# Easy_555_relay.net
KiCad netlist of a schematic drawn in EAGLE
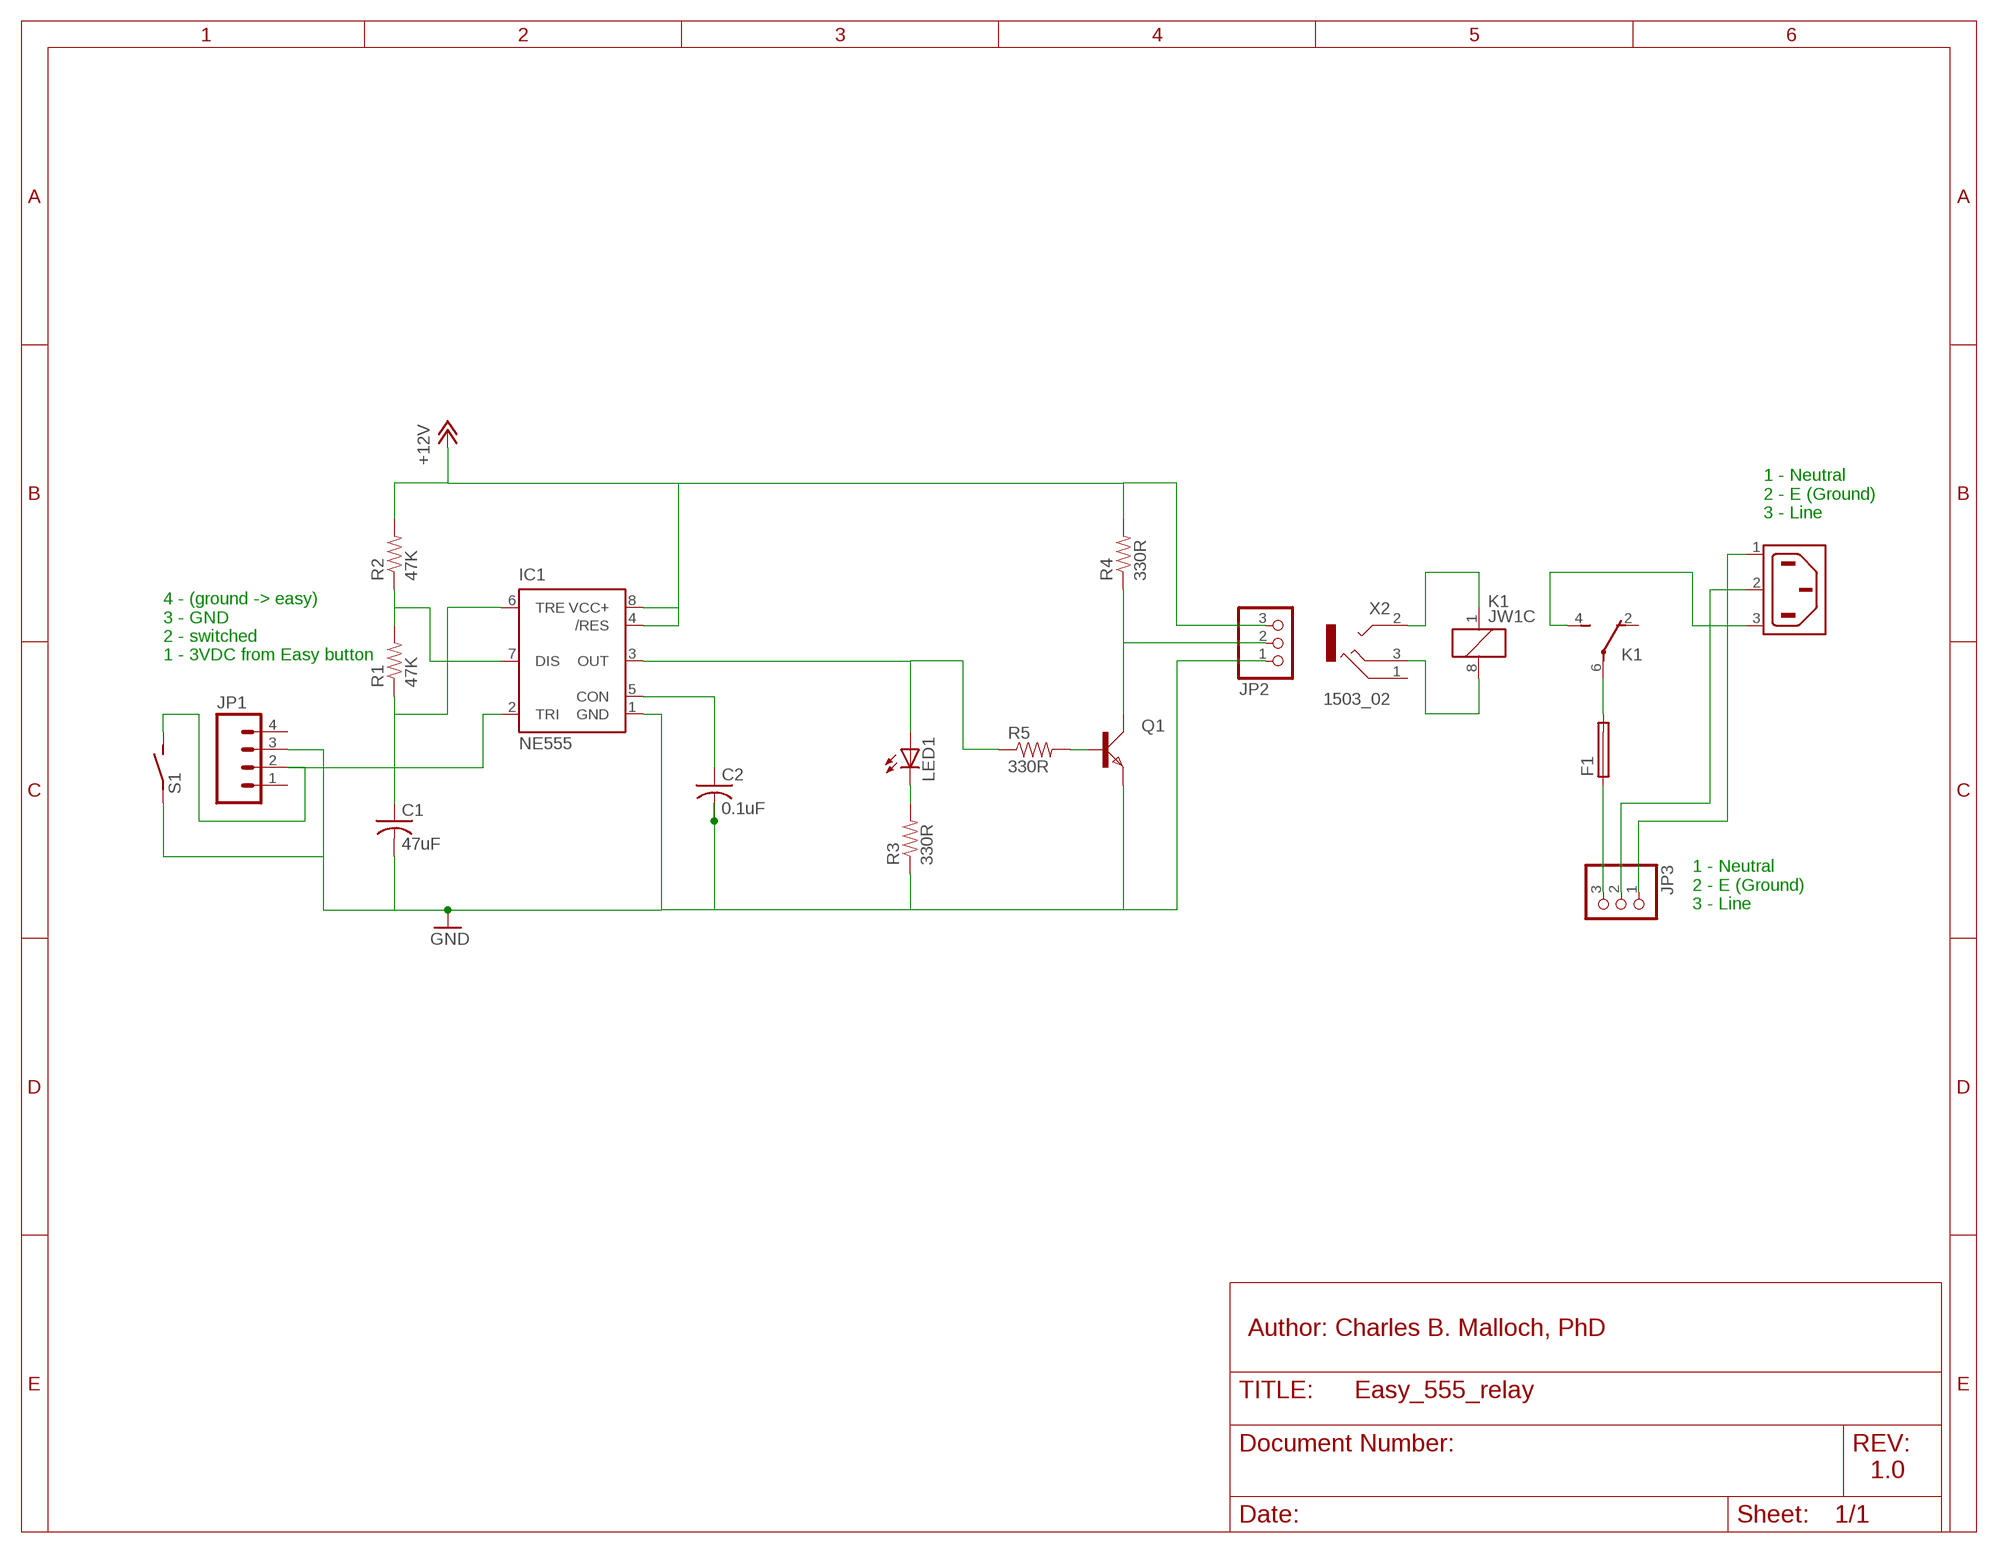
[diagram p0: schematic, sheet 1]

(export (version "E")
  (design (tool "Eeschema 10.0.6"))
  (components
    (comp (ref "C1")
      (value "47uF")
      (footprint "eagle-import:C050-030X075")
      (libsource (lib "eagle-import") (part "resistor_C-US050-030X075"))
    )
    (comp (ref "C2")
      (value "0.1uF")
      (footprint "eagle-import:C025-025X050")
      (libsource (lib "eagle-import") (part "C-US025-025X050"))
    )
    (comp (ref "F1")
      (value "GSH15")
      (footprint "eagle-import:GSH15")
      (fields (field (name "MPN") "64900001039"))
      (libsource (lib "eagle-import") (part "GSH15"))
    )
    (comp (ref "IC1")
      (value "NE555")
      (footprint "eagle-import:DIL-08")
      (fields (field (name "MF") "Arrow Electronics") (field (name "MPN") "NE555N"))
      (libsource (lib "eagle-import") (part "NE555"))
    )
    (comp (ref "JP1")
      (value "M04LOCK")
      (footprint "eagle-import:1X04_LOCK")
      (libsource (lib "eagle-import") (part "M04LOCK"))
    )
    (comp (ref "JP2")
      (value "PINHD-1X3")
      (footprint "eagle-import:1X03")
      (libsource (lib "eagle-import") (part "PINHD-1X3"))
    )
    (comp (ref "JP3")
      (value "PINHD-1X3")
      (footprint "eagle-import:1X03")
      (libsource (lib "eagle-import") (part "PINHD-1X3"))
    )
    (comp (ref "K1")
      (value "JW1C")
      (footprint "eagle-import:JW1C")
      (libsource (lib "eagle-import") (part "JW1C"))
    )
    (comp (ref "LED1")
      (value "LED3MM")
      (footprint "eagle-import:LED3MM")
      (libsource (lib "eagle-import") (part "LED3MM"))
    )
    (comp (ref "Q1")
      (value "2N3904-")
      (footprint "eagle-import:TO92D-")
      (libsource (lib "eagle-import") (part "2N3904-"))
    )
    (comp (ref "R1")
      (value "47K")
      (footprint "eagle-import:AXIAL-0.4")
      (libsource (lib "eagle-import") (part "RESISTORPTH-1/4W"))
    )
    (comp (ref "R2")
      (value "47K")
      (footprint "eagle-import:AXIAL-0.4")
      (libsource (lib "eagle-import") (part "RESISTORPTH-1/4W"))
    )
    (comp (ref "R3")
      (value "330R")
      (footprint "eagle-import:AXIAL-0.4")
      (libsource (lib "eagle-import") (part "RESISTORPTH-1/4W"))
    )
    (comp (ref "R4")
      (value "330R")
      (footprint "eagle-import:AXIAL-0.4")
      (libsource (lib "eagle-import") (part "RESISTORPTH-1/4W"))
    )
    (comp (ref "R5")
      (value "330R")
      (footprint "eagle-import:AXIAL-0.4")
      (libsource (lib "eagle-import") (part "RESISTORPTH-1/4W"))
    )
    (comp (ref "S1")
      (value "SPST2EVQPJ")
      (footprint "eagle-import:EVQPJ")
      (libsource (lib "eagle-import") (part "SPST2EVQPJ"))
    )
    (comp (ref "X1")
      (value "6ESRM-P")
      (footprint "eagle-import:6ESRM-P")
      (fields (field (name "MF") "TYCO ELECTRONICS"))
      (libsource (lib "eagle-import") (part "6ESRM-P"))
    )
    (comp (ref "X2")
      (value "1503_02")
      (footprint "eagle-import:1503_02")
      (libsource (lib "eagle-import") (part "1503_02"))
    )
  )
  (nets
    (net (code "1") (name "+12V") (class "Default")
      (node (ref "IC1") (pin "4") (pinfunction "/RES_4") (pintype "input"))
      (node (ref "IC1") (pin "8") (pinfunction "VCC+_8") (pintype "power_in"))
      (node (ref "JP2") (pin "3") (pinfunction "3_3") (pintype "passive"))
      (node (ref "R2") (pin "P$2") (pinfunction "2_P$2") (pintype "passive"))
      (node (ref "R4") (pin "P$2") (pinfunction "2_P$2") (pintype "passive"))
    )
    (net (code "2") (name "GND") (class "Default")
      (node (ref "C1") (pin "2") (pinfunction "2_2") (pintype "passive"))
      (node (ref "C2") (pin "2") (pinfunction "2_2") (pintype "passive"))
      (node (ref "IC1") (pin "1") (pinfunction "GND_1") (pintype "power_in"))
      (node (ref "JP1") (pin "3") (pinfunction "3_3") (pintype "passive"))
      (node (ref "JP2") (pin "1") (pinfunction "1_1") (pintype "passive"))
      (node (ref "Q1") (pin "E") (pinfunction "E_E") (pintype "passive"))
      (node (ref "R3") (pin "P$1") (pinfunction "1_P$1") (pintype "passive"))
      (node (ref "S1") (pin "A") (pinfunction "1_A") (pintype "passive"))
    )
    (net (code "3") (name "Net-(F1-Pad1)") (class "Default")
      (node (ref "F1") (pin "1") (pinfunction "1_1") (pintype "passive"))
      (node (ref "JP3") (pin "3") (pinfunction "3_3") (pintype "passive"))
    )
    (net (code "4") (name "Net-(IC1-CON)") (class "Default")
      (node (ref "C2") (pin "1") (pinfunction "1_1") (pintype "passive"))
      (node (ref "IC1") (pin "5") (pinfunction "CON_5") (pintype "input"))
    )
    (net (code "5") (name "Net-(IC1-DIS)") (class "Default")
      (node (ref "IC1") (pin "7") (pinfunction "DIS_7") (pintype "input"))
      (node (ref "R1") (pin "P$2") (pinfunction "2_P$2") (pintype "passive"))
      (node (ref "R2") (pin "P$1") (pinfunction "1_P$1") (pintype "passive"))
    )
    (net (code "6") (name "Net-(IC1-OUT)") (class "Default")
      (node (ref "IC1") (pin "3") (pinfunction "OUT_3") (pintype "output"))
      (node (ref "LED1") (pin "A") (pinfunction "A_A") (pintype "passive"))
      (node (ref "R5") (pin "P$1") (pinfunction "1_P$1") (pintype "passive"))
    )
    (net (code "7") (name "Net-(IC1-TRE)") (class "Default")
      (node (ref "C1") (pin "1") (pinfunction "1_1") (pintype "passive"))
      (node (ref "IC1") (pin "6") (pinfunction "TRE_6") (pintype "input"))
      (node (ref "R1") (pin "P$1") (pinfunction "1_P$1") (pintype "passive"))
    )
    (net (code "8") (name "Net-(IC1-TRI)") (class "Default")
      (node (ref "IC1") (pin "2") (pinfunction "TRI_2") (pintype "input"))
      (node (ref "JP1") (pin "2") (pinfunction "2_2") (pintype "passive"))
      (node (ref "S1") (pin "B") (pinfunction "2_B") (pintype "passive"))
    )
    (net (code "9") (name "Net-(K1-Pad1)") (class "Default")
      (node (ref "K1") (pin "1") (pinfunction "1_1") (pintype "passive"))
      (node (ref "X2") (pin "2") (pinfunction "2_2") (pintype "passive"))
    )
    (net (code "10") (name "Net-(K1A-P)") (class "Default")
      (node (ref "F1") (pin "2") (pinfunction "2_2") (pintype "passive"))
      (node (ref "K1") (pin "6") (pinfunction "P_6") (pintype "passive"))
    )
    (net (code "11") (name "Net-(K1A-S)") (class "Default")
      (node (ref "K1") (pin "4") (pinfunction "S_4") (pintype "passive"))
      (node (ref "X1") (pin "3") (pinfunction "AC2_3") (pintype "passive"))
    )
    (net (code "12") (name "Net-(K1B-2)") (class "Default")
      (node (ref "K1") (pin "8") (pinfunction "2_8") (pintype "passive"))
      (node (ref "X2") (pin "3") (pinfunction "3_3") (pintype "passive"))
    )
    (net (code "13") (name "Net-(LED1-C)") (class "Default")
      (node (ref "LED1") (pin "K") (pinfunction "C_K") (pintype "passive"))
      (node (ref "R3") (pin "P$2") (pinfunction "2_P$2") (pintype "passive"))
    )
    (net (code "14") (name "Net-(R4-1)") (class "Default")
      (node (ref "Q1") (pin "C") (pinfunction "C_C") (pintype "passive"))
      (node (ref "R4") (pin "P$1") (pinfunction "1_P$1") (pintype "passive"))
    )
    (net (code "15") (name "Net-(R5-2)") (class "Default")
      (node (ref "Q1") (pin "B") (pinfunction "B_B") (pintype "passive"))
      (node (ref "R5") (pin "P$2") (pinfunction "2_P$2") (pintype "passive"))
    )
    (net (code "16") (name "Net-(X1-AC1)") (class "Default")
      (node (ref "JP3") (pin "1") (pinfunction "1_1") (pintype "passive"))
      (node (ref "X1") (pin "1") (pinfunction "AC1_1") (pintype "passive"))
    )
    (net (code "17") (name "Net-(X1-SH)") (class "Default")
      (node (ref "JP3") (pin "2") (pinfunction "2_2") (pintype "passive"))
      (node (ref "X1") (pin "2") (pinfunction "SH_2") (pintype "passive"))
    )
    (net (code "18") (name "unconnected-(JP1-Pad1)") (class "Default")
      (node (ref "JP1") (pin "1") (pinfunction "1_1") (pintype "passive"))
    )
    (net (code "19") (name "unconnected-(JP1-Pad4)") (class "Default")
      (node (ref "JP1") (pin "4") (pinfunction "4_4") (pintype "passive"))
    )
    (net (code "20") (name "unconnected-(JP2-Pad2)") (class "Default")
      (node (ref "JP2") (pin "2") (pinfunction "2_2") (pintype "passive"))
    )
    (net (code "21") (name "unconnected-(K1A-O-Pad2)") (class "Default")
      (node (ref "K1") (pin "2") (pinfunction "O_2") (pintype "passive"))
    )
    (net (code "22") (name "unconnected-(X2-2-Pad2@2)") (class "Default")
      (node (ref "X2") (pin "2@2") (pinfunction "2_2@2") (pintype "passive"))
    )
    (net (code "23") (name "unconnected-(X2-Pad1)") (class "Default")
      (node (ref "X2") (pin "1") (pinfunction "1_1") (pintype "passive"))
    )
  )
)
